# Power_MPU.net
KiCad netlist of a schematic drawn in Altium Designer
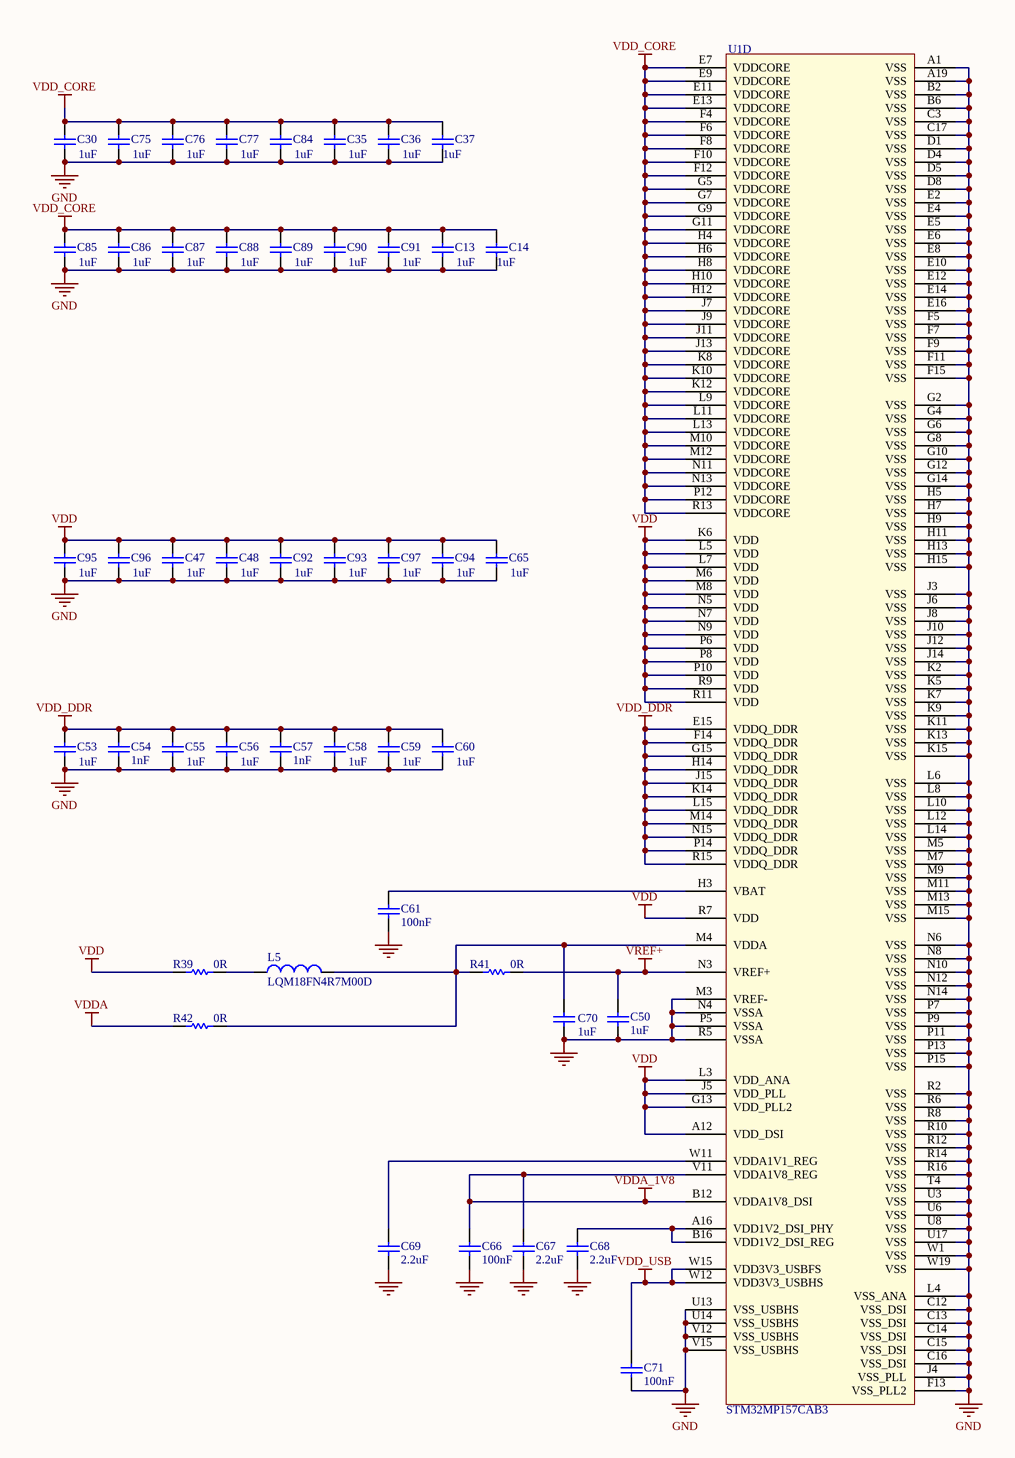
[diagram p0: Power_MPU.SchDoc]

(export (version "E")
  (design (tool "Eeschema 10.0.6"))
  (components
    (comp (ref "C13")
      (value "1uF")
      (footprint "C0402")
      (description "Capacitor, MLCC, 1uF, 6V3, X5R, 10%, 0402, T=0,5mm")
      (fields
        (field (name "INTERNAL_PART_NUMBER") "MCD-00095")
        (field (name "MANUFACTURER_PART_NUMBER") "GRM155R61E105KA12")
        (field (name "PROVIDED_BY") "SUBCO")
      )
      (libsource (lib "MCD_PARTS_database") (part "Capacitor"))
    )
    (comp (ref "C14")
      (value "1uF")
      (footprint "C0402")
      (description "Capacitor, MLCC, 1uF, 6V3, X5R, 10%, 0402, T=0,5mm")
      (fields
        (field (name "INTERNAL_PART_NUMBER") "MCD-00095")
        (field (name "MANUFACTURER_PART_NUMBER") "GRM155R61E105KA12")
        (field (name "PROVIDED_BY") "SUBCO")
      )
      (libsource (lib "MCD_PARTS_database") (part "Capacitor"))
    )
    (comp (ref "C30")
      (value "1uF")
      (footprint "C0402")
      (description "Capacitor, MLCC, 1uF, 6V3, X5R, 10%, 0402, T=0,5mm")
      (fields
        (field (name "INTERNAL_PART_NUMBER") "MCD-00095")
        (field (name "MANUFACTURER_PART_NUMBER") "GRM155R61E105KA12")
        (field (name "PROVIDED_BY") "SUBCO")
      )
      (libsource (lib "MCD_PARTS_database") (part "Capacitor"))
    )
    (comp (ref "C35")
      (value "1uF")
      (footprint "C0402")
      (description "Capacitor, MLCC, 1uF, 6V3, X5R, 10%, 0402, T=0,5mm")
      (fields
        (field (name "INTERNAL_PART_NUMBER") "MCD-00095")
        (field (name "MANUFACTURER_PART_NUMBER") "GRM155R61E105KA12")
        (field (name "PROVIDED_BY") "SUBCO")
      )
      (libsource (lib "MCD_PARTS_database") (part "Capacitor"))
    )
    (comp (ref "C36")
      (value "1uF")
      (footprint "C0402")
      (description "Capacitor, MLCC, 1uF, 6V3, X5R, 10%, 0402, T=0,5mm")
      (fields
        (field (name "INTERNAL_PART_NUMBER") "MCD-00095")
        (field (name "MANUFACTURER_PART_NUMBER") "GRM155R61E105KA12")
        (field (name "PROVIDED_BY") "SUBCO")
      )
      (libsource (lib "MCD_PARTS_database") (part "Capacitor"))
    )
    (comp (ref "C37")
      (value "1uF")
      (footprint "C0402")
      (description "Capacitor, MLCC, 1uF, 6V3, X5R, 10%, 0402, T=0,5mm")
      (fields
        (field (name "INTERNAL_PART_NUMBER") "MCD-00095")
        (field (name "MANUFACTURER_PART_NUMBER") "GRM155R61E105KA12")
        (field (name "PROVIDED_BY") "SUBCO")
      )
      (libsource (lib "MCD_PARTS_database") (part "Capacitor"))
    )
    (comp (ref "C47")
      (value "1uF")
      (footprint "C0402")
      (description "Capacitor, MLCC, 1uF, 6V3, X5R, 10%, 0402, T=0,5mm")
      (fields
        (field (name "INTERNAL_PART_NUMBER") "MCD-00095")
        (field (name "MANUFACTURER_PART_NUMBER") "GRM155R61E105KA12")
        (field (name "PROVIDED_BY") "SUBCO")
      )
      (libsource (lib "MCD_PARTS_database") (part "Capacitor"))
    )
    (comp (ref "C48")
      (value "1uF")
      (footprint "C0402")
      (description "Capacitor, MLCC, 1uF, 6V3, X5R, 10%, 0402, T=0,5mm")
      (fields
        (field (name "INTERNAL_PART_NUMBER") "MCD-00095")
        (field (name "MANUFACTURER_PART_NUMBER") "GRM155R61E105KA12")
        (field (name "PROVIDED_BY") "SUBCO")
      )
      (libsource (lib "MCD_PARTS_database") (part "Capacitor"))
    )
    (comp (ref "C50")
      (value "1uF")
      (footprint "C0402")
      (description "Capacitor, MLCC, 1uF, 6V3, X5R, 10%, 0402, T=0,5mm")
      (fields
        (field (name "INTERNAL_PART_NUMBER") "MCD-00095")
        (field (name "MANUFACTURER_PART_NUMBER") "GRM155R61E105KA12")
        (field (name "PROVIDED_BY") "SUBCO")
      )
      (libsource (lib "MCD_PARTS_database") (part "Capacitor"))
    )
    (comp (ref "C53")
      (value "1uF")
      (footprint "C0402")
      (description "Capacitor, MLCC, 1uF, 6V3, X5R, 10%, 0402, T=0,5mm")
      (fields
        (field (name "INTERNAL_PART_NUMBER") "MCD-00095")
        (field (name "MANUFACTURER_PART_NUMBER") "GRM155R61E105KA12")
        (field (name "PROVIDED_BY") "SUBCO")
      )
      (libsource (lib "MCD_PARTS_database") (part "Capacitor"))
    )
    (comp (ref "C54")
      (value "1nF")
      (footprint "C0402")
      (description "Capacitor, MLCC, 1nF, 16V, X7R, 10%, 0402, T=0.5mm")
      (fields
        (field (name "INTERNAL_PART_NUMBER") "MCD-00198")
        (field (name "MANUFACTURER_PART_NUMBER") "CC0402KRX7R7BB102")
        (field (name "PROVIDED_BY") "SUBCO")
      )
      (libsource (lib "MCD_PARTS_database") (part "Capacitor"))
    )
    (comp (ref "C55")
      (value "1uF")
      (footprint "C0402")
      (description "Capacitor, MLCC, 1uF, 6V3, X5R, 10%, 0402, T=0,5mm")
      (fields
        (field (name "INTERNAL_PART_NUMBER") "MCD-00095")
        (field (name "MANUFACTURER_PART_NUMBER") "GRM155R61E105KA12")
        (field (name "PROVIDED_BY") "SUBCO")
      )
      (libsource (lib "MCD_PARTS_database") (part "Capacitor"))
    )
    (comp (ref "C56")
      (value "1uF")
      (footprint "C0402")
      (description "Capacitor, MLCC, 1uF, 6V3, X5R, 10%, 0402, T=0,5mm")
      (fields
        (field (name "INTERNAL_PART_NUMBER") "MCD-00095")
        (field (name "MANUFACTURER_PART_NUMBER") "GRM155R61E105KA12")
        (field (name "PROVIDED_BY") "SUBCO")
      )
      (libsource (lib "MCD_PARTS_database") (part "Capacitor"))
    )
    (comp (ref "C57")
      (value "1nF")
      (footprint "C0402")
      (description "Capacitor, MLCC, 1nF, 16V, X7R, 10%, 0402, T=0.5mm")
      (fields
        (field (name "INTERNAL_PART_NUMBER") "MCD-00198")
        (field (name "MANUFACTURER_PART_NUMBER") "CC0402KRX7R7BB102")
        (field (name "PROVIDED_BY") "SUBCO")
      )
      (libsource (lib "MCD_PARTS_database") (part "Capacitor"))
    )
    (comp (ref "C58")
      (value "1uF")
      (footprint "C0402")
      (description "Capacitor, MLCC, 1uF, 6V3, X5R, 10%, 0402, T=0,5mm")
      (fields
        (field (name "INTERNAL_PART_NUMBER") "MCD-00095")
        (field (name "MANUFACTURER_PART_NUMBER") "GRM155R61E105KA12")
        (field (name "PROVIDED_BY") "SUBCO")
      )
      (libsource (lib "MCD_PARTS_database") (part "Capacitor"))
    )
    (comp (ref "C59")
      (value "1uF")
      (footprint "C0402")
      (description "Capacitor, MLCC, 1uF, 6V3, X5R, 10%, 0402, T=0,5mm")
      (fields
        (field (name "INTERNAL_PART_NUMBER") "MCD-00095")
        (field (name "MANUFACTURER_PART_NUMBER") "GRM155R61E105KA12")
        (field (name "PROVIDED_BY") "SUBCO")
      )
      (libsource (lib "MCD_PARTS_database") (part "Capacitor"))
    )
    (comp (ref "C60")
      (value "1uF")
      (footprint "C0402")
      (description "Capacitor, MLCC, 1uF, 6V3, X5R, 10%, 0402, T=0,5mm")
      (fields
        (field (name "INTERNAL_PART_NUMBER") "MCD-00095")
        (field (name "MANUFACTURER_PART_NUMBER") "GRM155R61E105KA12")
        (field (name "PROVIDED_BY") "SUBCO")
      )
      (libsource (lib "MCD_PARTS_database") (part "Capacitor"))
    )
    (comp (ref "C61")
      (value "100nF")
      (footprint "C0402")
      (description "Capacitor, MLCC, 100nF, 16V, X7R, 10%, 0402, T=0.5mm")
      (fields
        (field (name "INTERNAL_PART_NUMBER") "MCD-00006")
        (field (name "MANUFACTURER_PART_NUMBER") "CC0402KRX7R7BB104")
        (field (name "PROVIDED_BY") "SUBCO")
      )
      (libsource (lib "MCD_PARTS_database") (part "Capacitor"))
    )
    (comp (ref "C65")
      (value "1uF")
      (footprint "C0402")
      (description "Capacitor, MLCC, 1uF, 6V3, X5R, 10%, 0402, T=0,5mm")
      (fields
        (field (name "INTERNAL_PART_NUMBER") "MCD-00095")
        (field (name "MANUFACTURER_PART_NUMBER") "GRM155R61E105KA12")
        (field (name "PROVIDED_BY") "SUBCO")
      )
      (libsource (lib "MCD_PARTS_database") (part "Capacitor"))
    )
    (comp (ref "C66")
      (value "100nF")
      (footprint "C0402")
      (description "Capacitor, MLCC, 100nF, 16V, X7R, 10%, 0402, T=0.5mm")
      (fields
        (field (name "INTERNAL_PART_NUMBER") "MCD-00006")
        (field (name "MANUFACTURER_PART_NUMBER") "CC0402KRX7R7BB104")
        (field (name "PROVIDED_BY") "SUBCO")
      )
      (libsource (lib "MCD_PARTS_database") (part "Capacitor"))
    )
    (comp (ref "C67")
      (value "2.2uF")
      (footprint "C0402")
      (description "Capacitor,MLCC,2.2uF,6V3,X5R,10%,0402,T=0.5")
      (fields
        (field (name "INTERNAL_PART_NUMBER") "MCD-01823")
        (field (name "MANUFACTURER_PART_NUMBER") "GRM155R60J225KE95D")
        (field (name "PROVIDED_BY") "SUBCO")
      )
      (libsource (lib "MCD_PARTS_database") (part "Capacitor"))
    )
    (comp (ref "C68")
      (value "2.2uF")
      (footprint "C0402")
      (description "Capacitor,MLCC,2.2uF,6V3,X5R,10%,0402,T=0.5")
      (fields
        (field (name "INTERNAL_PART_NUMBER") "MCD-01823")
        (field (name "MANUFACTURER_PART_NUMBER") "GRM155R60J225KE95D")
        (field (name "PROVIDED_BY") "SUBCO")
      )
      (libsource (lib "MCD_PARTS_database") (part "Capacitor"))
    )
    (comp (ref "C69")
      (value "2.2uF")
      (footprint "C0402")
      (description "Capacitor,MLCC,2.2uF,6V3,X5R,10%,0402,T=0.5")
      (fields
        (field (name "INTERNAL_PART_NUMBER") "MCD-01823")
        (field (name "MANUFACTURER_PART_NUMBER") "GRM155R60J225KE95D")
        (field (name "PROVIDED_BY") "SUBCO")
      )
      (libsource (lib "MCD_PARTS_database") (part "Capacitor"))
    )
    (comp (ref "C70")
      (value "1uF")
      (footprint "C0402")
      (description "Capacitor, MLCC, 1uF, 6V3, X5R, 10%, 0402, T=0,5mm")
      (fields
        (field (name "INTERNAL_PART_NUMBER") "MCD-00095")
        (field (name "MANUFACTURER_PART_NUMBER") "GRM155R61E105KA12")
        (field (name "PROVIDED_BY") "SUBCO")
      )
      (libsource (lib "MCD_PARTS_database") (part "Capacitor"))
    )
    (comp (ref "C71")
      (value "100nF")
      (footprint "C0402")
      (description "Capacitor, MLCC, 100nF, 16V, X7R, 10%, 0402, T=0.5mm")
      (fields
        (field (name "INTERNAL_PART_NUMBER") "MCD-00006")
        (field (name "MANUFACTURER_PART_NUMBER") "CC0402KRX7R7BB104")
        (field (name "PROVIDED_BY") "SUBCO")
      )
      (libsource (lib "MCD_PARTS_database") (part "Capacitor"))
    )
    (comp (ref "C75")
      (value "1uF")
      (footprint "C0402")
      (description "Capacitor, MLCC, 1uF, 6V3, X5R, 10%, 0402, T=0,5mm")
      (fields
        (field (name "INTERNAL_PART_NUMBER") "MCD-00095")
        (field (name "MANUFACTURER_PART_NUMBER") "GRM155R61E105KA12")
        (field (name "PROVIDED_BY") "SUBCO")
      )
      (libsource (lib "MCD_PARTS_database") (part "Capacitor"))
    )
    (comp (ref "C76")
      (value "1uF")
      (footprint "C0402")
      (description "Capacitor, MLCC, 1uF, 6V3, X5R, 10%, 0402, T=0,5mm")
      (fields
        (field (name "INTERNAL_PART_NUMBER") "MCD-00095")
        (field (name "MANUFACTURER_PART_NUMBER") "GRM155R61E105KA12")
        (field (name "PROVIDED_BY") "SUBCO")
      )
      (libsource (lib "MCD_PARTS_database") (part "Capacitor"))
    )
    (comp (ref "C77")
      (value "1uF")
      (footprint "C0402")
      (description "Capacitor, MLCC, 1uF, 6V3, X5R, 10%, 0402, T=0,5mm")
      (fields
        (field (name "INTERNAL_PART_NUMBER") "MCD-00095")
        (field (name "MANUFACTURER_PART_NUMBER") "GRM155R61E105KA12")
        (field (name "PROVIDED_BY") "SUBCO")
      )
      (libsource (lib "MCD_PARTS_database") (part "Capacitor"))
    )
    (comp (ref "C84")
      (value "1uF")
      (footprint "C0402")
      (description "Capacitor, MLCC, 1uF, 6V3, X5R, 10%, 0402, T=0,5mm")
      (fields
        (field (name "INTERNAL_PART_NUMBER") "MCD-00095")
        (field (name "MANUFACTURER_PART_NUMBER") "GRM155R61E105KA12")
        (field (name "PROVIDED_BY") "SUBCO")
      )
      (libsource (lib "MCD_PARTS_database") (part "Capacitor"))
    )
    (comp (ref "C85")
      (value "1uF")
      (footprint "C0402")
      (description "Capacitor, MLCC, 1uF, 6V3, X5R, 10%, 0402, T=0,5mm")
      (fields
        (field (name "INTERNAL_PART_NUMBER") "MCD-00095")
        (field (name "MANUFACTURER_PART_NUMBER") "GRM155R61E105KA12")
        (field (name "PROVIDED_BY") "SUBCO")
      )
      (libsource (lib "MCD_PARTS_database") (part "Capacitor"))
    )
    (comp (ref "C86")
      (value "1uF")
      (footprint "C0402")
      (description "Capacitor, MLCC, 1uF, 6V3, X5R, 10%, 0402, T=0,5mm")
      (fields
        (field (name "INTERNAL_PART_NUMBER") "MCD-00095")
        (field (name "MANUFACTURER_PART_NUMBER") "GRM155R61E105KA12")
        (field (name "PROVIDED_BY") "SUBCO")
      )
      (libsource (lib "MCD_PARTS_database") (part "Capacitor"))
    )
    (comp (ref "C87")
      (value "1uF")
      (footprint "C0402")
      (description "Capacitor, MLCC, 1uF, 6V3, X5R, 10%, 0402, T=0,5mm")
      (fields
        (field (name "INTERNAL_PART_NUMBER") "MCD-00095")
        (field (name "MANUFACTURER_PART_NUMBER") "GRM155R61E105KA12")
        (field (name "PROVIDED_BY") "SUBCO")
      )
      (libsource (lib "MCD_PARTS_database") (part "Capacitor"))
    )
    (comp (ref "C88")
      (value "1uF")
      (footprint "C0402")
      (description "Capacitor, MLCC, 1uF, 6V3, X5R, 10%, 0402, T=0,5mm")
      (fields
        (field (name "INTERNAL_PART_NUMBER") "MCD-00095")
        (field (name "MANUFACTURER_PART_NUMBER") "GRM155R61E105KA12")
        (field (name "PROVIDED_BY") "SUBCO")
      )
      (libsource (lib "MCD_PARTS_database") (part "Capacitor"))
    )
    (comp (ref "C89")
      (value "1uF")
      (footprint "C0402")
      (description "Capacitor, MLCC, 1uF, 6V3, X5R, 10%, 0402, T=0,5mm")
      (fields
        (field (name "INTERNAL_PART_NUMBER") "MCD-00095")
        (field (name "MANUFACTURER_PART_NUMBER") "GRM155R61E105KA12")
        (field (name "PROVIDED_BY") "SUBCO")
      )
      (libsource (lib "MCD_PARTS_database") (part "Capacitor"))
    )
    (comp (ref "C90")
      (value "1uF")
      (footprint "C0402")
      (description "Capacitor, MLCC, 1uF, 6V3, X5R, 10%, 0402, T=0,5mm")
      (fields
        (field (name "INTERNAL_PART_NUMBER") "MCD-00095")
        (field (name "MANUFACTURER_PART_NUMBER") "GRM155R61E105KA12")
        (field (name "PROVIDED_BY") "SUBCO")
      )
      (libsource (lib "MCD_PARTS_database") (part "Capacitor"))
    )
    (comp (ref "C91")
      (value "1uF")
      (footprint "C0402")
      (description "Capacitor, MLCC, 1uF, 6V3, X5R, 10%, 0402, T=0,5mm")
      (fields
        (field (name "INTERNAL_PART_NUMBER") "MCD-00095")
        (field (name "MANUFACTURER_PART_NUMBER") "GRM155R61E105KA12")
        (field (name "PROVIDED_BY") "SUBCO")
      )
      (libsource (lib "MCD_PARTS_database") (part "Capacitor"))
    )
    (comp (ref "C92")
      (value "1uF")
      (footprint "C0402")
      (description "Capacitor, MLCC, 1uF, 6V3, X5R, 10%, 0402, T=0,5mm")
      (fields
        (field (name "INTERNAL_PART_NUMBER") "MCD-00095")
        (field (name "MANUFACTURER_PART_NUMBER") "GRM155R61E105KA12")
        (field (name "PROVIDED_BY") "SUBCO")
      )
      (libsource (lib "MCD_PARTS_database") (part "Capacitor"))
    )
    (comp (ref "C93")
      (value "1uF")
      (footprint "C0402")
      (description "Capacitor, MLCC, 1uF, 6V3, X5R, 10%, 0402, T=0,5mm")
      (fields
        (field (name "INTERNAL_PART_NUMBER") "MCD-00095")
        (field (name "MANUFACTURER_PART_NUMBER") "GRM155R61E105KA12")
        (field (name "PROVIDED_BY") "SUBCO")
      )
      (libsource (lib "MCD_PARTS_database") (part "Capacitor"))
    )
    (comp (ref "C94")
      (value "1uF")
      (footprint "C0402")
      (description "Capacitor, MLCC, 1uF, 6V3, X5R, 10%, 0402, T=0,5mm")
      (fields
        (field (name "INTERNAL_PART_NUMBER") "MCD-00095")
        (field (name "MANUFACTURER_PART_NUMBER") "GRM155R61E105KA12")
        (field (name "PROVIDED_BY") "SUBCO")
      )
      (libsource (lib "MCD_PARTS_database") (part "Capacitor"))
    )
    (comp (ref "C95")
      (value "1uF")
      (footprint "C0402")
      (description "Capacitor, MLCC, 1uF, 6V3, X5R, 10%, 0402, T=0,5mm")
      (fields
        (field (name "INTERNAL_PART_NUMBER") "MCD-00095")
        (field (name "MANUFACTURER_PART_NUMBER") "GRM155R61E105KA12")
        (field (name "PROVIDED_BY") "SUBCO")
      )
      (libsource (lib "MCD_PARTS_database") (part "Capacitor"))
    )
    (comp (ref "C96")
      (value "1uF")
      (footprint "C0402")
      (description "Capacitor, MLCC, 1uF, 6V3, X5R, 10%, 0402, T=0,5mm")
      (fields
        (field (name "INTERNAL_PART_NUMBER") "MCD-00095")
        (field (name "MANUFACTURER_PART_NUMBER") "GRM155R61E105KA12")
        (field (name "PROVIDED_BY") "SUBCO")
      )
      (libsource (lib "MCD_PARTS_database") (part "Capacitor"))
    )
    (comp (ref "C97")
      (value "1uF")
      (footprint "C0402")
      (description "Capacitor, MLCC, 1uF, 6V3, X5R, 10%, 0402, T=0,5mm")
      (fields
        (field (name "INTERNAL_PART_NUMBER") "MCD-00095")
        (field (name "MANUFACTURER_PART_NUMBER") "GRM155R61E105KA12")
        (field (name "PROVIDED_BY") "SUBCO")
      )
      (libsource (lib "MCD_PARTS_database") (part "Capacitor"))
    )
    (comp (ref "L5")
      (value "LQM18FN4R7M00D")
      (footprint "L0603_H0P8")
      (description "IND 4.7uH 20% 80mA 600mhom 0603")
      (fields
        (field (name "INTERNAL_PART_NUMBER") "MCD-01134")
        (field (name "MANUFACTURER") "MURATA")
        (field (name "PROVIDED_BY") "SUBCO")
      )
      (libsource (lib "MCD_PARTS_database") (part "LQM18FN4R7M00D"))
    )
    (comp (ref "R39")
      (value "0R")
      (footprint "R0402")
      (description "Resistor,0R,0402,5%,1/16W")
      (fields
        (field (name "INTERNAL_PART_NUMBER") "MCD-00052")
        (field (name "MANUFACTURER_PART_NUMBER") "RC0402JR-070RL")
        (field (name "PROVIDED_BY") "SUBCO")
      )
      (libsource (lib "MCD_PARTS_database") (part "Resistor"))
    )
    (comp (ref "R41")
      (value "0R")
      (footprint "R0402")
      (description "Resistor,0R,0402,5%,1/16W")
      (fields
        (field (name "INTERNAL_PART_NUMBER") "MCD-00052")
        (field (name "MANUFACTURER_PART_NUMBER") "RC0402JR-070RL")
        (field (name "PROVIDED_BY") "SUBCO")
      )
      (libsource (lib "MCD_PARTS_database") (part "Resistor"))
    )
    (comp (ref "R42")
      (value "0R")
      (footprint "R0402")
      (description "Resistor,0R,0402,5%,1/16W")
      (fields
        (field (name "INTERNAL_PART_NUMBER") "MCD-00052")
        (field (name "MANUFACTURER_PART_NUMBER") "RC0402JR-070RL")
        (field (name "PROVIDED_BY") "SUBCO")
      )
      (libsource (lib "MCD_PARTS_database") (part "Resistor"))
    )
    (comp (ref "U1")
      (value "STM32MP157CAB3")
      (footprint "ICC_LFBGA354_16X16_STM32MP157CAB3_P080")
      (description "MPU LFBGA 16x16x1.271 PITCH 0.8 mm secure boot + crypto")
      (fields
        (field (name "INTERNAL_PART_NUMBER") "MCD-01805")
        (field (name "MANUFACTURER") "STMICROELECTRONICS")
        (field (name "PROVIDED_BY") "SUBCO with ST control")
      )
      (libsource (lib "MCD_PARTS_database") (part "STM32MP157CAB3"))
    )
  )
  (nets
    (net (code "1") (name "GND") (class "Default")
      (node (ref "C13") (pin "1") (pinfunction "1_1") (pintype "passive"))
      (node (ref "C14") (pin "1") (pinfunction "1_1") (pintype "passive"))
      (node (ref "C30") (pin "1") (pinfunction "1_1") (pintype "passive"))
      (node (ref "C35") (pin "1") (pinfunction "1_1") (pintype "passive"))
      (node (ref "C36") (pin "1") (pinfunction "1_1") (pintype "passive"))
      (node (ref "C37") (pin "1") (pinfunction "1_1") (pintype "passive"))
      (node (ref "C47") (pin "1") (pinfunction "1_1") (pintype "passive"))
      (node (ref "C48") (pin "1") (pinfunction "1_1") (pintype "passive"))
      (node (ref "C50") (pin "1") (pinfunction "1_1") (pintype "passive"))
      (node (ref "C53") (pin "1") (pinfunction "1_1") (pintype "passive"))
      (node (ref "C54") (pin "1") (pinfunction "1_1") (pintype "passive"))
      (node (ref "C55") (pin "1") (pinfunction "1_1") (pintype "passive"))
      (node (ref "C56") (pin "1") (pinfunction "1_1") (pintype "passive"))
      (node (ref "C57") (pin "1") (pinfunction "1_1") (pintype "passive"))
      (node (ref "C58") (pin "1") (pinfunction "1_1") (pintype "passive"))
      (node (ref "C59") (pin "1") (pinfunction "1_1") (pintype "passive"))
      (node (ref "C60") (pin "1") (pinfunction "1_1") (pintype "passive"))
      (node (ref "C61") (pin "1") (pinfunction "1_1") (pintype "passive"))
      (node (ref "C65") (pin "1") (pinfunction "1_1") (pintype "passive"))
      (node (ref "C66") (pin "1") (pinfunction "1_1") (pintype "passive"))
      (node (ref "C67") (pin "1") (pinfunction "1_1") (pintype "passive"))
      (node (ref "C68") (pin "1") (pinfunction "1_1") (pintype "passive"))
      (node (ref "C69") (pin "1") (pinfunction "1_1") (pintype "passive"))
      (node (ref "C70") (pin "1") (pinfunction "1_1") (pintype "passive"))
      (node (ref "C71") (pin "1") (pinfunction "1_1") (pintype "passive"))
      (node (ref "C75") (pin "1") (pinfunction "1_1") (pintype "passive"))
      (node (ref "C76") (pin "1") (pinfunction "1_1") (pintype "passive"))
      (node (ref "C77") (pin "1") (pinfunction "1_1") (pintype "passive"))
      (node (ref "C84") (pin "1") (pinfunction "1_1") (pintype "passive"))
      (node (ref "C85") (pin "1") (pinfunction "1_1") (pintype "passive"))
      (node (ref "C86") (pin "1") (pinfunction "1_1") (pintype "passive"))
      (node (ref "C87") (pin "1") (pinfunction "1_1") (pintype "passive"))
      (node (ref "C88") (pin "1") (pinfunction "1_1") (pintype "passive"))
      (node (ref "C89") (pin "1") (pinfunction "1_1") (pintype "passive"))
      (node (ref "C90") (pin "1") (pinfunction "1_1") (pintype "passive"))
      (node (ref "C91") (pin "1") (pinfunction "1_1") (pintype "passive"))
      (node (ref "C92") (pin "1") (pinfunction "1_1") (pintype "passive"))
      (node (ref "C93") (pin "1") (pinfunction "1_1") (pintype "passive"))
      (node (ref "C94") (pin "1") (pinfunction "1_1") (pintype "passive"))
      (node (ref "C95") (pin "1") (pinfunction "1_1") (pintype "passive"))
      (node (ref "C96") (pin "1") (pinfunction "1_1") (pintype "passive"))
      (node (ref "C97") (pin "1") (pinfunction "1_1") (pintype "passive"))
      (node (ref "U1") (pin "A1") (pinfunction "VSS_A1") (pintype "passive"))
      (node (ref "U1") (pin "A19") (pinfunction "VSS_A19") (pintype "passive"))
      (node (ref "U1") (pin "B2") (pinfunction "VSS_B2") (pintype "passive"))
      (node (ref "U1") (pin "B6") (pinfunction "VSS_B6") (pintype "passive"))
      (node (ref "U1") (pin "C12") (pinfunction "VSS_DSI_C12") (pintype "passive"))
      (node (ref "U1") (pin "C13") (pinfunction "VSS_DSI_C13") (pintype "passive"))
      (node (ref "U1") (pin "C14") (pinfunction "VSS_DSI_C14") (pintype "passive"))
      (node (ref "U1") (pin "C15") (pinfunction "VSS_DSI_C15") (pintype "passive"))
      (node (ref "U1") (pin "C16") (pinfunction "VSS_DSI_C16") (pintype "passive"))
      (node (ref "U1") (pin "C17") (pinfunction "VSS_C17") (pintype "passive"))
      (node (ref "U1") (pin "C3") (pinfunction "VSS_C3") (pintype "passive"))
      (node (ref "U1") (pin "D1") (pinfunction "VSS_D1") (pintype "passive"))
      (node (ref "U1") (pin "D4") (pinfunction "VSS_D4") (pintype "passive"))
      (node (ref "U1") (pin "D5") (pinfunction "VSS_D5") (pintype "passive"))
      (node (ref "U1") (pin "D8") (pinfunction "VSS_D8") (pintype "passive"))
      (node (ref "U1") (pin "E10") (pinfunction "VSS_E10") (pintype "passive"))
      (node (ref "U1") (pin "E12") (pinfunction "VSS_E12") (pintype "passive"))
      (node (ref "U1") (pin "E14") (pinfunction "VSS_E14") (pintype "passive"))
      (node (ref "U1") (pin "E16") (pinfunction "VSS_E16") (pintype "passive"))
      (node (ref "U1") (pin "E2") (pinfunction "VSS_E2") (pintype "passive"))
      (node (ref "U1") (pin "E4") (pinfunction "VSS_E4") (pintype "passive"))
      (node (ref "U1") (pin "E5") (pinfunction "VSS_E5") (pintype "passive"))
      (node (ref "U1") (pin "E6") (pinfunction "VSS_E6") (pintype "passive"))
      (node (ref "U1") (pin "E8") (pinfunction "VSS_E8") (pintype "passive"))
      (node (ref "U1") (pin "F11") (pinfunction "VSS_F11") (pintype "passive"))
      (node (ref "U1") (pin "F13") (pinfunction "VSS_PLL2_F13") (pintype "passive"))
      (node (ref "U1") (pin "F15") (pinfunction "VSS_F15") (pintype "passive"))
      (node (ref "U1") (pin "F5") (pinfunction "VSS_F5") (pintype "passive"))
      (node (ref "U1") (pin "F7") (pinfunction "VSS_F7") (pintype "passive"))
      (node (ref "U1") (pin "F9") (pinfunction "VSS_F9") (pintype "passive"))
      (node (ref "U1") (pin "G10") (pinfunction "VSS_G10") (pintype "passive"))
      (node (ref "U1") (pin "G12") (pinfunction "VSS_G12") (pintype "passive"))
      (node (ref "U1") (pin "G14") (pinfunction "VSS_G14") (pintype "passive"))
      (node (ref "U1") (pin "G2") (pinfunction "VSS_G2") (pintype "passive"))
      (node (ref "U1") (pin "G4") (pinfunction "VSS_G4") (pintype "passive"))
      (node (ref "U1") (pin "G6") (pinfunction "VSS_G6") (pintype "passive"))
      (node (ref "U1") (pin "G8") (pinfunction "VSS_G8") (pintype "passive"))
      (node (ref "U1") (pin "H11") (pinfunction "VSS_H11") (pintype "passive"))
      (node (ref "U1") (pin "H13") (pinfunction "VSS_H13") (pintype "passive"))
      (node (ref "U1") (pin "H15") (pinfunction "VSS_H15") (pintype "passive"))
      (node (ref "U1") (pin "H5") (pinfunction "VSS_H5") (pintype "passive"))
      (node (ref "U1") (pin "H7") (pinfunction "VSS_H7") (pintype "passive"))
      (node (ref "U1") (pin "H9") (pinfunction "VSS_H9") (pintype "passive"))
      (node (ref "U1") (pin "J10") (pinfunction "VSS_J10") (pintype "passive"))
      (node (ref "U1") (pin "J12") (pinfunction "VSS_J12") (pintype "passive"))
      (node (ref "U1") (pin "J14") (pinfunction "VSS_J14") (pintype "passive"))
      (node (ref "U1") (pin "J3") (pinfunction "VSS_J3") (pintype "passive"))
      (node (ref "U1") (pin "J4") (pinfunction "VSS_PLL_J4") (pintype "passive"))
      (node (ref "U1") (pin "J6") (pinfunction "VSS_J6") (pintype "passive"))
      (node (ref "U1") (pin "J8") (pinfunction "VSS_J8") (pintype "passive"))
      (node (ref "U1") (pin "K11") (pinfunction "VSS_K11") (pintype "passive"))
      (node (ref "U1") (pin "K13") (pinfunction "VSS_K13") (pintype "passive"))
      (node (ref "U1") (pin "K15") (pinfunction "VSS_K15") (pintype "passive"))
      (node (ref "U1") (pin "K2") (pinfunction "VSS_K2") (pintype "passive"))
      (node (ref "U1") (pin "K5") (pinfunction "VSS_K5") (pintype "passive"))
      (node (ref "U1") (pin "K7") (pinfunction "VSS_K7") (pintype "passive"))
      (node (ref "U1") (pin "K9") (pinfunction "VSS_K9") (pintype "passive"))
      (node (ref "U1") (pin "L10") (pinfunction "VSS_L10") (pintype "passive"))
      (node (ref "U1") (pin "L12") (pinfunction "VSS_L12") (pintype "passive"))
      (node (ref "U1") (pin "L14") (pinfunction "VSS_L14") (pintype "passive"))
      (node (ref "U1") (pin "L4") (pinfunction "VSS_ANA_L4") (pintype "passive"))
      (node (ref "U1") (pin "L6") (pinfunction "VSS_L6") (pintype "passive"))
      (node (ref "U1") (pin "L8") (pinfunction "VSS_L8") (pintype "passive"))
      (node (ref "U1") (pin "M11") (pinfunction "VSS_M11") (pintype "passive"))
      (node (ref "U1") (pin "M13") (pinfunction "VSS_M13") (pintype "passive"))
      (node (ref "U1") (pin "M15") (pinfunction "VSS_M15") (pintype "passive"))
      (node (ref "U1") (pin "M3") (pinfunction "VREF-_M3") (pintype "passive"))
      (node (ref "U1") (pin "M5") (pinfunction "VSS_M5") (pintype "passive"))
      (node (ref "U1") (pin "M7") (pinfunction "VSS_M7") (pintype "passive"))
      (node (ref "U1") (pin "M9") (pinfunction "VSS_M9") (pintype "passive"))
      (node (ref "U1") (pin "N10") (pinfunction "VSS_N10") (pintype "passive"))
      (node (ref "U1") (pin "N12") (pinfunction "VSS_N12") (pintype "passive"))
      (node (ref "U1") (pin "N14") (pinfunction "VSS_N14") (pintype "passive"))
      (node (ref "U1") (pin "N4") (pinfunction "VSSA_N4") (pintype "passive"))
      (node (ref "U1") (pin "N6") (pinfunction "VSS_N6") (pintype "passive"))
      (node (ref "U1") (pin "N8") (pinfunction "VSS_N8") (pintype "passive"))
      (node (ref "U1") (pin "P11") (pinfunction "VSS_P11") (pintype "passive"))
      (node (ref "U1") (pin "P13") (pinfunction "VSS_P13") (pintype "passive"))
      (node (ref "U1") (pin "P15") (pinfunction "VSS_P15") (pintype "passive"))
      (node (ref "U1") (pin "P5") (pinfunction "VSSA_P5") (pintype "passive"))
      (node (ref "U1") (pin "P7") (pinfunction "VSS_P7") (pintype "passive"))
      (node (ref "U1") (pin "P9") (pinfunction "VSS_P9") (pintype "passive"))
      (node (ref "U1") (pin "R10") (pinfunction "VSS_R10") (pintype "passive"))
      (node (ref "U1") (pin "R12") (pinfunction "VSS_R12") (pintype "passive"))
      (node (ref "U1") (pin "R14") (pinfunction "VSS_R14") (pintype "passive"))
      (node (ref "U1") (pin "R16") (pinfunction "VSS_R16") (pintype "passive"))
      (node (ref "U1") (pin "R2") (pinfunction "VSS_R2") (pintype "passive"))
      (node (ref "U1") (pin "R5") (pinfunction "VSSA_R5") (pintype "passive"))
      (node (ref "U1") (pin "R6") (pinfunction "VSS_R6") (pintype "passive"))
      (node (ref "U1") (pin "R8") (pinfunction "VSS_R8") (pintype "passive"))
      (node (ref "U1") (pin "T4") (pinfunction "VSS_T4") (pintype "passive"))
      (node (ref "U1") (pin "U13") (pinfunction "VSS_USBHS_U13") (pintype "passive"))
      (node (ref "U1") (pin "U14") (pinfunction "VSS_USBHS_U14") (pintype "passive"))
      (node (ref "U1") (pin "U17") (pinfunction "VSS_U17") (pintype "passive"))
      (node (ref "U1") (pin "U3") (pinfunction "VSS_U3") (pintype "passive"))
      (node (ref "U1") (pin "U6") (pinfunction "VSS_U6") (pintype "passive"))
      (node (ref "U1") (pin "U8") (pinfunction "VSS_U8") (pintype "passive"))
      (node (ref "U1") (pin "V12") (pinfunction "VSS_USBHS_V12") (pintype "passive"))
      (node (ref "U1") (pin "V15") (pinfunction "VSS_USBHS_V15") (pintype "passive"))
      (node (ref "U1") (pin "W1") (pinfunction "VSS_W1") (pintype "passive"))
      (node (ref "U1") (pin "W19") (pinfunction "VSS_W19") (pintype "passive"))
    )
    (net (code "2") (name "Net-(L5-Pad1)") (class "Default")
      (node (ref "L5") (pin "1") (pinfunction "1_1") (pintype "passive"))
      (node (ref "R39") (pin "2") (pinfunction "2_2") (pintype "passive"))
    )
    (net (code "3") (name "Net-(U1D-VBAT)") (class "Default")
      (node (ref "C61") (pin "2") (pinfunction "2_2") (pintype "passive"))
      (node (ref "U1") (pin "H3") (pinfunction "VBAT_H3") (pintype "passive"))
    )
    (net (code "4") (name "Net-(U1D-VDD1V2_DSI_PHY)") (class "Default")
      (node (ref "C68") (pin "2") (pinfunction "2_2") (pintype "passive"))
      (node (ref "U1") (pin "A16") (pinfunction "VDD1V2_DSI_PHY_A16") (pintype "passive"))
      (node (ref "U1") (pin "B16") (pinfunction "VDD1V2_DSI_REG_B16") (pintype "passive"))
    )
    (net (code "5") (name "Net-(U1D-VDDA)") (class "Default")
      (node (ref "C70") (pin "2") (pinfunction "2_2") (pintype "passive"))
      (node (ref "L5") (pin "2") (pinfunction "2_2") (pintype "passive"))
      (node (ref "R41") (pin "1") (pinfunction "1_1") (pintype "passive"))
      (node (ref "R42") (pin "2") (pinfunction "2_2") (pintype "passive"))
      (node (ref "U1") (pin "M4") (pinfunction "VDDA_M4") (pintype "passive"))
    )
    (net (code "6") (name "Net-(U1D-VDDA1V1_REG)") (class "Default")
      (node (ref "C69") (pin "2") (pinfunction "2_2") (pintype "passive"))
      (node (ref "U1") (pin "W11") (pinfunction "VDDA1V1_REG_W11") (pintype "passive"))
    )
    (net (code "7") (name "VDD") (class "Default")
      (node (ref "C47") (pin "2") (pinfunction "2_2") (pintype "passive"))
      (node (ref "C48") (pin "2") (pinfunction "2_2") (pintype "passive"))
      (node (ref "C65") (pin "2") (pinfunction "2_2") (pintype "passive"))
      (node (ref "C92") (pin "2") (pinfunction "2_2") (pintype "passive"))
      (node (ref "C93") (pin "2") (pinfunction "2_2") (pintype "passive"))
      (node (ref "C94") (pin "2") (pinfunction "2_2") (pintype "passive"))
      (node (ref "C95") (pin "2") (pinfunction "2_2") (pintype "passive"))
      (node (ref "C96") (pin "2") (pinfunction "2_2") (pintype "passive"))
      (node (ref "C97") (pin "2") (pinfunction "2_2") (pintype "passive"))
      (node (ref "R39") (pin "1") (pinfunction "1_1") (pintype "passive"))
      (node (ref "U1") (pin "A12") (pinfunction "VDD_DSI_A12") (pintype "passive"))
      (node (ref "U1") (pin "G13") (pinfunction "VDD_PLL2_G13") (pintype "passive"))
      (node (ref "U1") (pin "J5") (pinfunction "VDD_PLL_J5") (pintype "passive"))
      (node (ref "U1") (pin "K6") (pinfunction "VDD_K6") (pintype "passive"))
      (node (ref "U1") (pin "L3") (pinfunction "VDD_ANA_L3") (pintype "passive"))
      (node (ref "U1") (pin "L5") (pinfunction "VDD_L5") (pintype "passive"))
      (node (ref "U1") (pin "L7") (pinfunction "VDD_L7") (pintype "passive"))
      (node (ref "U1") (pin "M6") (pinfunction "VDD_M6") (pintype "passive"))
      (node (ref "U1") (pin "M8") (pinfunction "VDD_M8") (pintype "passive"))
      (node (ref "U1") (pin "N5") (pinfunction "VDD_N5") (pintype "passive"))
      (node (ref "U1") (pin "N7") (pinfunction "VDD_N7") (pintype "passive"))
      (node (ref "U1") (pin "N9") (pinfunction "VDD_N9") (pintype "passive"))
      (node (ref "U1") (pin "P10") (pinfunction "VDD_P10") (pintype "passive"))
      (node (ref "U1") (pin "P6") (pinfunction "VDD_P6") (pintype "passive"))
      (node (ref "U1") (pin "P8") (pinfunction "VDD_P8") (pintype "passive"))
      (node (ref "U1") (pin "R11") (pinfunction "VDD_R11") (pintype "passive"))
      (node (ref "U1") (pin "R7") (pinfunction "VDD_R7") (pintype "passive"))
      (node (ref "U1") (pin "R9") (pinfunction "VDD_R9") (pintype "passive"))
    )
    (net (code "8") (name "VDDA") (class "Default")
      (node (ref "R42") (pin "1") (pinfunction "1_1") (pintype "passive"))
    )
    (net (code "9") (name "VDDA_1V8") (class "Default")
      (node (ref "C66") (pin "2") (pinfunction "2_2") (pintype "passive"))
      (node (ref "C67") (pin "2") (pinfunction "2_2") (pintype "passive"))
      (node (ref "U1") (pin "B12") (pinfunction "VDDA1V8_DSI_B12") (pintype "passive"))
      (node (ref "U1") (pin "V11") (pinfunction "VDDA1V8_REG_V11") (pintype "passive"))
    )
    (net (code "10") (name "VDD_CORE") (class "Default")
      (node (ref "C13") (pin "2") (pinfunction "2_2") (pintype "passive"))
      (node (ref "C14") (pin "2") (pinfunction "2_2") (pintype "passive"))
      (node (ref "C30") (pin "2") (pinfunction "2_2") (pintype "passive"))
      (node (ref "C35") (pin "2") (pinfunction "2_2") (pintype "passive"))
      (node (ref "C36") (pin "2") (pinfunction "2_2") (pintype "passive"))
      (node (ref "C37") (pin "2") (pinfunction "2_2") (pintype "passive"))
      (node (ref "C75") (pin "2") (pinfunction "2_2") (pintype "passive"))
      (node (ref "C76") (pin "2") (pinfunction "2_2") (pintype "passive"))
      (node (ref "C77") (pin "2") (pinfunction "2_2") (pintype "passive"))
      (node (ref "C84") (pin "2") (pinfunction "2_2") (pintype "passive"))
      (node (ref "C85") (pin "2") (pinfunction "2_2") (pintype "passive"))
      (node (ref "C86") (pin "2") (pinfunction "2_2") (pintype "passive"))
      (node (ref "C87") (pin "2") (pinfunction "2_2") (pintype "passive"))
      (node (ref "C88") (pin "2") (pinfunction "2_2") (pintype "passive"))
      (node (ref "C89") (pin "2") (pinfunction "2_2") (pintype "passive"))
      (node (ref "C90") (pin "2") (pinfunction "2_2") (pintype "passive"))
      (node (ref "C91") (pin "2") (pinfunction "2_2") (pintype "passive"))
      (node (ref "U1") (pin "E11") (pinfunction "VDDCORE_E11") (pintype "passive"))
      (node (ref "U1") (pin "E13") (pinfunction "VDDCORE_E13") (pintype "passive"))
      (node (ref "U1") (pin "E7") (pinfunction "VDDCORE_E7") (pintype "passive"))
      (node (ref "U1") (pin "E9") (pinfunction "VDDCORE_E9") (pintype "passive"))
      (node (ref "U1") (pin "F10") (pinfunction "VDDCORE_F10") (pintype "passive"))
      (node (ref "U1") (pin "F12") (pinfunction "VDDCORE_F12") (pintype "passive"))
      (node (ref "U1") (pin "F4") (pinfunction "VDDCORE_F4") (pintype "passive"))
      (node (ref "U1") (pin "F6") (pinfunction "VDDCORE_F6") (pintype "passive"))
      (node (ref "U1") (pin "F8") (pinfunction "VDDCORE_F8") (pintype "passive"))
      (node (ref "U1") (pin "G11") (pinfunction "VDDCORE_G11") (pintype "passive"))
      (node (ref "U1") (pin "G5") (pinfunction "VDDCORE_G5") (pintype "passive"))
      (node (ref "U1") (pin "G7") (pinfunction "VDDCORE_G7") (pintype "passive"))
      (node (ref "U1") (pin "G9") (pinfunction "VDDCORE_G9") (pintype "passive"))
      (node (ref "U1") (pin "H10") (pinfunction "VDDCORE_H10") (pintype "passive"))
      (node (ref "U1") (pin "H12") (pinfunction "VDDCORE_H12") (pintype "passive"))
      (node (ref "U1") (pin "H4") (pinfunction "VDDCORE_H4") (pintype "passive"))
      (node (ref "U1") (pin "H6") (pinfunction "VDDCORE_H6") (pintype "passive"))
      (node (ref "U1") (pin "H8") (pinfunction "VDDCORE_H8") (pintype "passive"))
      (node (ref "U1") (pin "J11") (pinfunction "VDDCORE_J11") (pintype "passive"))
      (node (ref "U1") (pin "J13") (pinfunction "VDDCORE_J13") (pintype "passive"))
      (node (ref "U1") (pin "J7") (pinfunction "VDDCORE_J7") (pintype "passive"))
      (node (ref "U1") (pin "J9") (pinfunction "VDDCORE_J9") (pintype "passive"))
      (node (ref "U1") (pin "K10") (pinfunction "VDDCORE_K10") (pintype "passive"))
      (node (ref "U1") (pin "K12") (pinfunction "VDDCORE_K12") (pintype "passive"))
      (node (ref "U1") (pin "K8") (pinfunction "VDDCORE_K8") (pintype "passive"))
      (node (ref "U1") (pin "L11") (pinfunction "VDDCORE_L11") (pintype "passive"))
      (node (ref "U1") (pin "L13") (pinfunction "VDDCORE_L13") (pintype "passive"))
      (node (ref "U1") (pin "L9") (pinfunction "VDDCORE_L9") (pintype "passive"))
      (node (ref "U1") (pin "M10") (pinfunction "VDDCORE_M10") (pintype "passive"))
      (node (ref "U1") (pin "M12") (pinfunction "VDDCORE_M12") (pintype "passive"))
      (node (ref "U1") (pin "N11") (pinfunction "VDDCORE_N11") (pintype "passive"))
      (node (ref "U1") (pin "N13") (pinfunction "VDDCORE_N13") (pintype "passive"))
      (node (ref "U1") (pin "P12") (pinfunction "VDDCORE_P12") (pintype "passive"))
      (node (ref "U1") (pin "R13") (pinfunction "VDDCORE_R13") (pintype "passive"))
    )
    (net (code "11") (name "VDD_DDR") (class "Default")
      (node (ref "C53") (pin "2") (pinfunction "2_2") (pintype "passive"))
      (node (ref "C54") (pin "2") (pinfunction "2_2") (pintype "passive"))
      (node (ref "C55") (pin "2") (pinfunction "2_2") (pintype "passive"))
      (node (ref "C56") (pin "2") (pinfunction "2_2") (pintype "passive"))
      (node (ref "C57") (pin "2") (pinfunction "2_2") (pintype "passive"))
      (node (ref "C58") (pin "2") (pinfunction "2_2") (pintype "passive"))
      (node (ref "C59") (pin "2") (pinfunction "2_2") (pintype "passive"))
      (node (ref "C60") (pin "2") (pinfunction "2_2") (pintype "passive"))
      (node (ref "U1") (pin "E15") (pinfunction "VDDQ_DDR_E15") (pintype "passive"))
      (node (ref "U1") (pin "F14") (pinfunction "VDDQ_DDR_F14") (pintype "passive"))
      (node (ref "U1") (pin "G15") (pinfunction "VDDQ_DDR_G15") (pintype "passive"))
      (node (ref "U1") (pin "H14") (pinfunction "VDDQ_DDR_H14") (pintype "passive"))
      (node (ref "U1") (pin "J15") (pinfunction "VDDQ_DDR_J15") (pintype "passive"))
      (node (ref "U1") (pin "K14") (pinfunction "VDDQ_DDR_K14") (pintype "passive"))
      (node (ref "U1") (pin "L15") (pinfunction "VDDQ_DDR_L15") (pintype "passive"))
      (node (ref "U1") (pin "M14") (pinfunction "VDDQ_DDR_M14") (pintype "passive"))
      (node (ref "U1") (pin "N15") (pinfunction "VDDQ_DDR_N15") (pintype "passive"))
      (node (ref "U1") (pin "P14") (pinfunction "VDDQ_DDR_P14") (pintype "passive"))
      (node (ref "U1") (pin "R15") (pinfunction "VDDQ_DDR_R15") (pintype "passive"))
    )
    (net (code "12") (name "VDD_USB") (class "Default")
      (node (ref "C71") (pin "2") (pinfunction "2_2") (pintype "passive"))
      (node (ref "U1") (pin "W12") (pinfunction "VDD3V3_USBHS_W12") (pintype "passive"))
      (node (ref "U1") (pin "W15") (pinfunction "VDD3V3_USBFS_W15") (pintype "passive"))
    )
    (net (code "13") (name "VREF+") (class "Default")
      (node (ref "C50") (pin "2") (pinfunction "2_2") (pintype "passive"))
      (node (ref "R41") (pin "2") (pinfunction "2_2") (pintype "passive"))
      (node (ref "U1") (pin "N3") (pinfunction "VREF+_N3") (pintype "passive"))
    )
  )
)
